# SCH_HTC_led_chaser_2025-11-01.net
KiCad netlist of a schematic drawn in EasyEDA
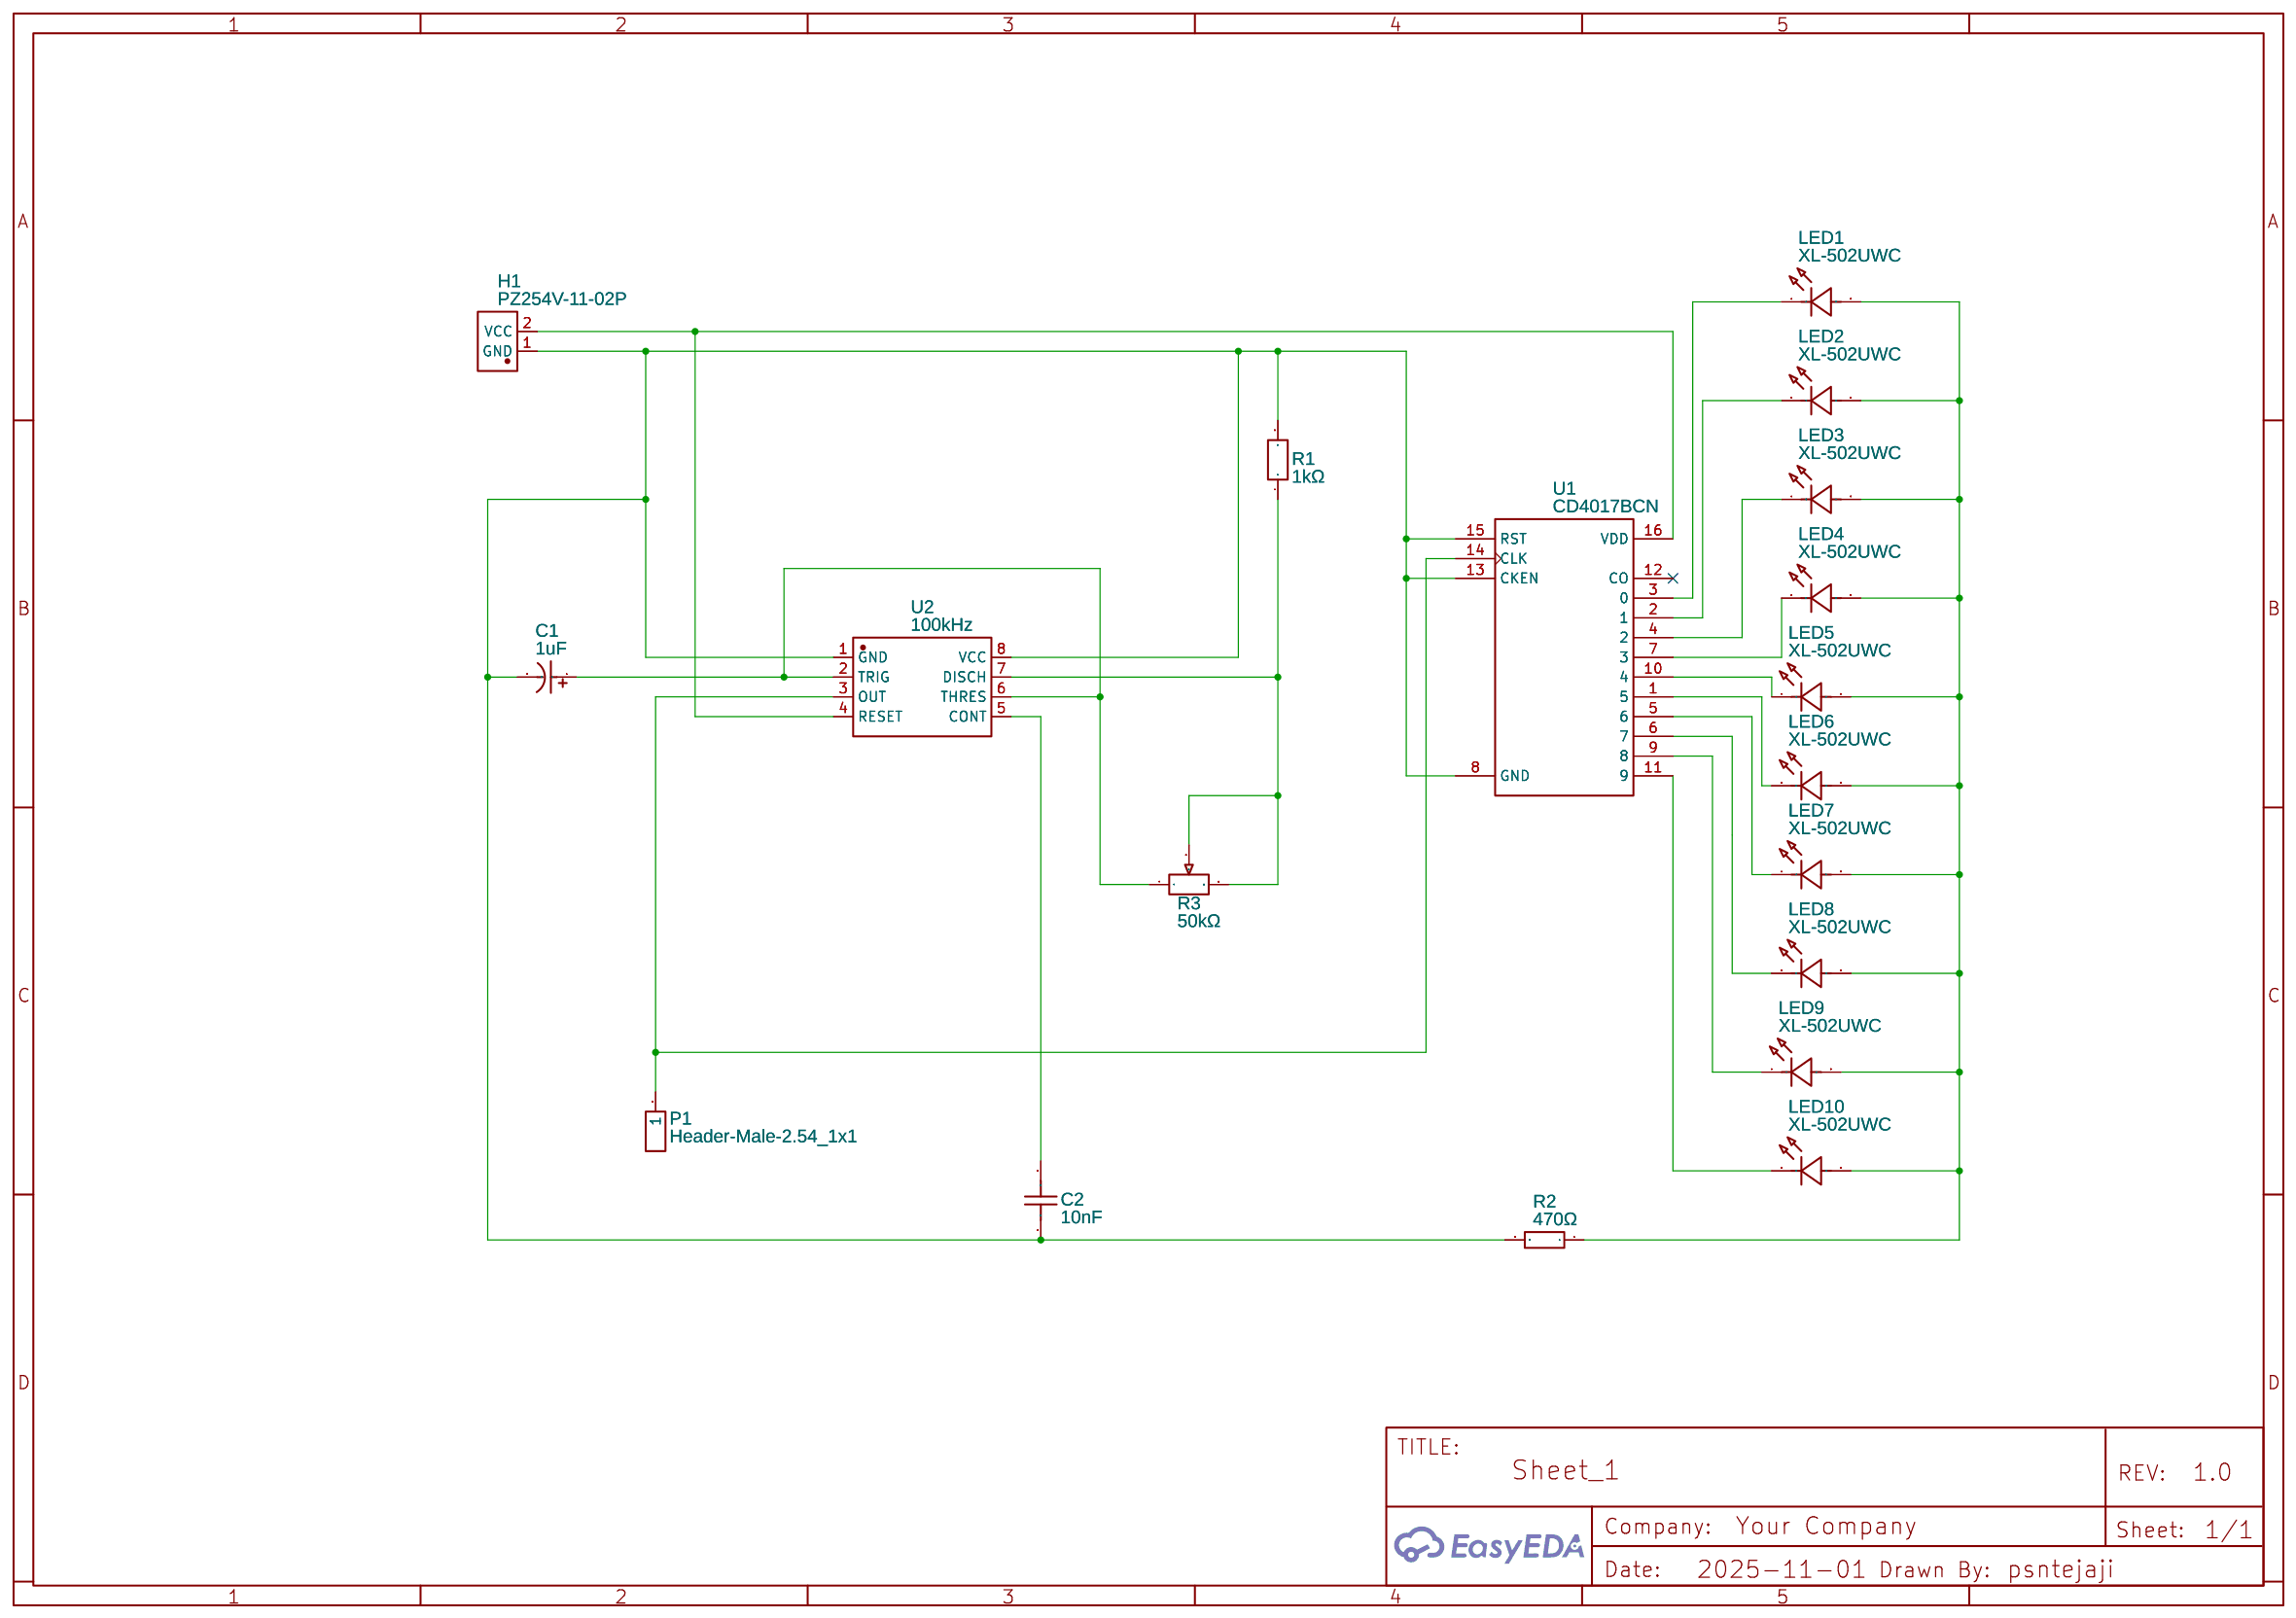
[diagram p0: schematic sheet]

(export (version "E")
  (design (tool "Eeschema 10.0.6"))
  (components
    (comp (ref "C1")
      (value "1uF")
      (fields (field (name "Manufacturer Part") "KF010M050C110A") (field (name "Manufacturer") "CapXon(丰宾)"))
      (libsource (lib "") (part "KF010M050C110A"))
    )
    (comp (ref "C2")
      (value "10nF")
      (fields (field (name "Manufacturer Part") "N09F1B103MN0B0S0N0") (field (name "Manufacturer") "STE(松田)"))
      (libsource (lib "") (part "N09F1B103MN0B0S0N0"))
    )
    (comp (ref "H1")
      (value "PZ254V-11-02P")
      (fields (field (name "Manufacturer") "XFCN(兴飞)"))
      (libsource (lib "") (part "PZ254V-11-02P"))
    )
    (comp (ref "LED1")
      (value "XL-502UWC")
      (fields (field (name "Manufacturer") "XINGLIGHT(成兴光)"))
      (libsource (lib "") (part "XL-502UWC"))
    )
    (comp (ref "LED2")
      (value "XL-502UWC")
      (fields (field (name "Manufacturer") "XINGLIGHT(成兴光)"))
      (libsource (lib "") (part "XL-502UWC"))
    )
    (comp (ref "LED3")
      (value "XL-502UWC")
      (fields (field (name "Manufacturer") "XINGLIGHT(成兴光)"))
      (libsource (lib "") (part "XL-502UWC"))
    )
    (comp (ref "LED4")
      (value "XL-502UWC")
      (fields (field (name "Manufacturer") "XINGLIGHT(成兴光)"))
      (libsource (lib "") (part "XL-502UWC"))
    )
    (comp (ref "LED5")
      (value "XL-502UWC")
      (fields (field (name "Manufacturer") "XINGLIGHT(成兴光)"))
      (libsource (lib "") (part "XL-502UWC"))
    )
    (comp (ref "LED6")
      (value "XL-502UWC")
      (fields (field (name "Manufacturer") "XINGLIGHT(成兴光)"))
      (libsource (lib "") (part "XL-502UWC"))
    )
    (comp (ref "LED7")
      (value "XL-502UWC")
      (fields (field (name "Manufacturer") "XINGLIGHT(成兴光)"))
      (libsource (lib "") (part "XL-502UWC"))
    )
    (comp (ref "LED8")
      (value "XL-502UWC")
      (fields (field (name "Manufacturer") "XINGLIGHT(成兴光)"))
      (libsource (lib "") (part "XL-502UWC"))
    )
    (comp (ref "LED9")
      (value "XL-502UWC")
      (fields (field (name "Manufacturer") "XINGLIGHT(成兴光)"))
      (libsource (lib "") (part "XL-502UWC"))
    )
    (comp (ref "LED10")
      (value "XL-502UWC")
      (fields (field (name "Manufacturer") "XINGLIGHT(成兴光)"))
      (libsource (lib "") (part "XL-502UWC"))
    )
    (comp (ref "P1")
      (value "Header-Male-2.54_1x1")
      (fields (field (name "Manufacturer Part") "2.54-1*1P针") (field (name "Manufacturer") "BOOMELE(博穆精密)"))
      (libsource (lib "") (part "Header-Male-2.54_1x1"))
    )
    (comp (ref "R1")
      (value "1kΩ")
      (fields (field (name "Manufacturer Part") "MF1/4W-1KΩ±1%T52") (field (name "Manufacturer") "华星机电"))
      (libsource (lib "") (part "MF1/4W-1KΩ±1%T52"))
    )
    (comp (ref "R2")
      (value "470Ω")
      (fields
        (field (name "Manufacturer Part") "MFR0W4F4700A50")
        (field (name "Manufacturer") "UNI-ROYAL(厚声)")
      )
      (libsource (lib "") (part "MFR0W4F4700A50"))
    )
    (comp (ref "R3")
      (value "50kΩ")
      (fields (field (name "Manufacturer Part") "3296X-1-503") (field (name "Manufacturer") "BOCHEN(博晨)"))
      (libsource (lib "") (part "3296X-1-503_C118912"))
    )
    (comp (ref "U1") (value "CD4017BCN") (libsource (lib "") (part "CD4017BCN")))
    (comp (ref "U2")
      (value "100kHz")
      (fields (field (name "Manufacturer Part") "NE555P") (field (name "Manufacturer") "TI(德州仪器)"))
      (libsource (lib "") (part "NE555P"))
    )
  )
  (nets
    (net (code "1") (name "Net-(H1-GND)") (class "Default")
      (node (ref "C1") (pin "2") (pinfunction "2_2") (pintype "input"))
      (node (ref "C2") (pin "1") (pinfunction "1_1") (pintype "unspecified"))
      (node (ref "H1") (pin "1") (pinfunction "GND_1") (pintype "unspecified"))
      (node (ref "R1") (pin "2") (pinfunction "2_2") (pintype "unspecified"))
      (node (ref "R2") (pin "2") (pinfunction "2_2") (pintype "input"))
      (node (ref "U1") (pin "13") (pinfunction "CKEN_13") (pintype "unspecified"))
      (node (ref "U1") (pin "15") (pinfunction "RST_15") (pintype "unspecified"))
      (node (ref "U1") (pin "8") (pinfunction "GND_8") (pintype "passive"))
      (node (ref "U2") (pin "1") (pinfunction "GND_1") (pintype "unspecified"))
      (node (ref "U2") (pin "8") (pinfunction "VCC_8") (pintype "unspecified"))
    )
    (net (code "2") (name "Net-(H1-VCC)") (class "Default")
      (node (ref "H1") (pin "2") (pinfunction "VCC_2") (pintype "unspecified"))
      (node (ref "U1") (pin "16") (pinfunction "VDD_16") (pintype "passive"))
      (node (ref "U2") (pin "4") (pinfunction "RESET_4") (pintype "unspecified"))
    )
    (net (code "3") (name "Net-(LED1-A)") (class "Default")
      (node (ref "LED1") (pin "2") (pinfunction "A_2") (pintype "unspecified"))
      (node (ref "LED10") (pin "2") (pinfunction "A_2") (pintype "unspecified"))
      (node (ref "LED2") (pin "2") (pinfunction "A_2") (pintype "unspecified"))
      (node (ref "LED3") (pin "2") (pinfunction "A_2") (pintype "unspecified"))
      (node (ref "LED4") (pin "2") (pinfunction "A_2") (pintype "unspecified"))
      (node (ref "LED5") (pin "2") (pinfunction "A_2") (pintype "unspecified"))
      (node (ref "LED6") (pin "2") (pinfunction "A_2") (pintype "unspecified"))
      (node (ref "LED7") (pin "2") (pinfunction "A_2") (pintype "unspecified"))
      (node (ref "LED8") (pin "2") (pinfunction "A_2") (pintype "unspecified"))
      (node (ref "LED9") (pin "2") (pinfunction "A_2") (pintype "unspecified"))
      (node (ref "R2") (pin "1") (pinfunction "1_1") (pintype "input"))
    )
    (net (code "4") (name "Net-(LED1-K)") (class "Default")
      (node (ref "LED1") (pin "1") (pinfunction "K_1") (pintype "unspecified"))
      (node (ref "U1") (pin "3") (pinfunction "0_3") (pintype "output"))
    )
    (net (code "5") (name "Net-(LED2-K)") (class "Default")
      (node (ref "LED2") (pin "1") (pinfunction "K_1") (pintype "unspecified"))
      (node (ref "U1") (pin "2") (pinfunction "1_2") (pintype "output"))
    )
    (net (code "6") (name "Net-(LED3-K)") (class "Default")
      (node (ref "LED3") (pin "1") (pinfunction "K_1") (pintype "unspecified"))
      (node (ref "U1") (pin "4") (pinfunction "2_4") (pintype "output"))
    )
    (net (code "7") (name "Net-(LED4-K)") (class "Default")
      (node (ref "LED4") (pin "1") (pinfunction "K_1") (pintype "unspecified"))
      (node (ref "U1") (pin "7") (pinfunction "3_7") (pintype "output"))
    )
    (net (code "8") (name "Net-(LED5-K)") (class "Default")
      (node (ref "LED5") (pin "1") (pinfunction "K_1") (pintype "unspecified"))
      (node (ref "U1") (pin "10") (pinfunction "4_10") (pintype "output"))
    )
    (net (code "9") (name "Net-(LED6-K)") (class "Default")
      (node (ref "LED6") (pin "1") (pinfunction "K_1") (pintype "unspecified"))
      (node (ref "U1") (pin "1") (pinfunction "5_1") (pintype "output"))
    )
    (net (code "10") (name "Net-(LED7-K)") (class "Default")
      (node (ref "LED7") (pin "1") (pinfunction "K_1") (pintype "unspecified"))
      (node (ref "U1") (pin "5") (pinfunction "6_5") (pintype "output"))
    )
    (net (code "11") (name "Net-(LED8-K)") (class "Default")
      (node (ref "LED8") (pin "1") (pinfunction "K_1") (pintype "unspecified"))
      (node (ref "U1") (pin "6") (pinfunction "7_6") (pintype "output"))
    )
    (net (code "12") (name "Net-(LED9-K)") (class "Default")
      (node (ref "LED9") (pin "1") (pinfunction "K_1") (pintype "unspecified"))
      (node (ref "U1") (pin "9") (pinfunction "8_9") (pintype "output"))
    )
    (net (code "13") (name "Net-(LED10-K)") (class "Default")
      (node (ref "LED10") (pin "1") (pinfunction "K_1") (pintype "unspecified"))
      (node (ref "U1") (pin "11") (pinfunction "9_11") (pintype "output"))
    )
    (net (code "14") (name "Net-(U1-CLK)") (class "Default")
      (node (ref "P1") (pin "1") (pinfunction "1_1") (pintype "input"))
      (node (ref "U1") (pin "14") (pinfunction "CLK_14") (pintype "unspecified"))
      (node (ref "U2") (pin "3") (pinfunction "OUT_3") (pintype "unspecified"))
    )
    (net (code "15") (name "Net-(U2-CONT)") (class "Default")
      (node (ref "C2") (pin "2") (pinfunction "2_2") (pintype "unspecified"))
      (node (ref "U2") (pin "5") (pinfunction "CONT_5") (pintype "unspecified"))
    )
    (net (code "16") (name "Net-(U2-DISCH)") (class "Default")
      (node (ref "R1") (pin "1") (pinfunction "1_1") (pintype "unspecified"))
      (node (ref "R3") (pin "2") (pinfunction "2_2") (pintype "input"))
      (node (ref "R3") (pin "3") (pinfunction "3_3") (pintype "input"))
      (node (ref "U2") (pin "7") (pinfunction "DISCH_7") (pintype "unspecified"))
    )
    (net (code "17") (name "Net-(U2-THRES)") (class "Default")
      (node (ref "C1") (pin "1") (pinfunction "1_1") (pintype "input"))
      (node (ref "R3") (pin "1") (pinfunction "1_1") (pintype "input"))
      (node (ref "U2") (pin "2") (pinfunction "TRIG_2") (pintype "unspecified"))
      (node (ref "U2") (pin "6") (pinfunction "THRES_6") (pintype "unspecified"))
    )
    (net (code "18") (name "unconnected-(U1-CO-Pad12)") (class "Default")
      (node (ref "U1") (pin "12") (pinfunction "CO_12") (pintype "output+no_connect"))
    )
  )
)
